# Sheet_1_2025-10-18.net
KiCad netlist of a schematic drawn in Altium Designer
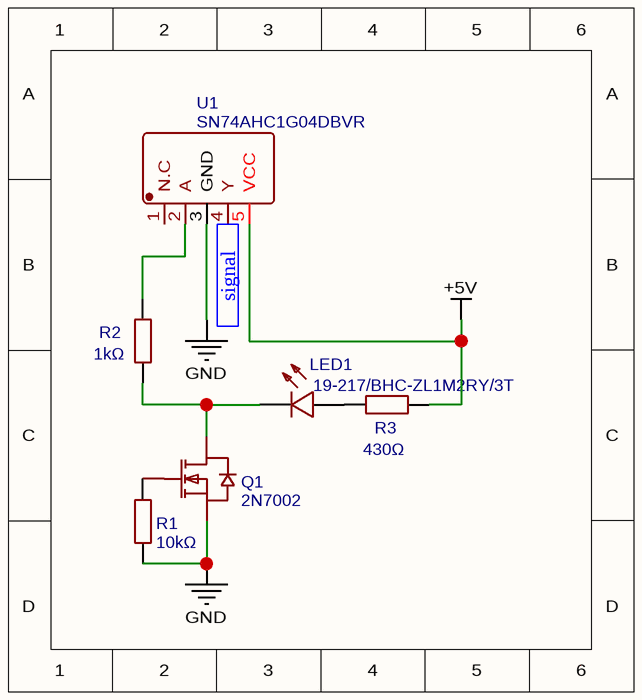
[diagram p0: Sheet_1_2025-10-18.schdoc]

(export (version "E")
  (design (tool "Eeschema 10.0.6"))
  (components
    (comp (ref "LED1")
      (value "19-217/BHC-ZL1M2RY/3T")
      (fields (field (name "MANUFACTURER") "EVERLIGHT"))
      (libsource (lib "altium-import") (part "root_0_19-217/BHC-ZL1M2RY/3T_"))
    )
    (comp (ref "Q1")
      (value "2N7002")
      (fields (field (name "MANUFACTURER") "CJ"))
      (libsource (lib "altium-import") (part "root_0_2N7002_"))
    )
    (comp (ref "R1")
      (value "10kΩ")
      (fields (field (name "MANUFACTURER") "UniOhm") (field (name "MANUFACTURER PART") "0402WGF1002TCE"))
      (libsource (lib "altium-import") (part "root_1_10kΩ_"))
    )
    (comp (ref "R2")
      (value "1kΩ")
      (fields (field (name "MANUFACTURER") "UniOhm") (field (name "MANUFACTURER PART") "0402WGF1001TCE"))
      (libsource (lib "altium-import") (part "root_3_1kΩ_"))
    )
    (comp (ref "R3")
      (value "430Ω")
      (fields (field (name "MANUFACTURER") "UniOhm") (field (name "MANUFACTURER PART") "0603WAF4300T5E"))
      (libsource (lib "altium-import") (part "root_0_430Ω_"))
    )
    (comp (ref "U1")
      (value "SN74AHC1G04DBVR")
      (fields (field (name "MANUFACTURER") "TI"))
      (libsource (lib "altium-import") (part "root_1_SN74AHC1G04DBVR_"))
    )
  )
  (nets
    (net (code "1") (name "+5V") (class "Default")
      (node (ref "R3") (pin "2") (pinfunction "2_2") (pintype "passive"))
      (node (ref "U1") (pin "5") (pinfunction "VCC_5") (pintype "passive"))
    )
    (net (code "2") (name "/signal") (class "Default")
      (node (ref "U1") (pin "4") (pinfunction "Y_4") (pintype "passive"))
    )
    (net (code "3") (name "GND") (class "Default")
      (node (ref "Q1") (pin "2") (pinfunction "S_2") (pintype "passive"))
      (node (ref "R1") (pin "1") (pinfunction "1_1") (pintype "passive"))
      (node (ref "U1") (pin "3") (pinfunction "GND_3") (pintype "passive"))
    )
    (net (code "4") (name "Net-(LED1-A)") (class "Default")
      (node (ref "LED1") (pin "1") (pinfunction "A_1") (pintype "passive"))
      (node (ref "R3") (pin "1") (pinfunction "1_1") (pintype "passive"))
    )
    (net (code "5") (name "Net-(LED1-C)") (class "Default")
      (node (ref "LED1") (pin "2") (pinfunction "C_2") (pintype "passive"))
      (node (ref "Q1") (pin "3") (pinfunction "D_3") (pintype "passive"))
      (node (ref "R2") (pin "2") (pinfunction "2_2") (pintype "passive"))
    )
    (net (code "6") (name "Net-(Q1-G)") (class "Default")
      (node (ref "Q1") (pin "1") (pinfunction "G_1") (pintype "passive"))
      (node (ref "R1") (pin "2") (pinfunction "2_2") (pintype "passive"))
    )
    (net (code "7") (name "Net-(U1-A)") (class "Default")
      (node (ref "R2") (pin "1") (pinfunction "1_1") (pintype "passive"))
      (node (ref "U1") (pin "2") (pinfunction "A_2") (pintype "passive"))
    )
    (net (code "8") (name "unconnected-(U1-N.C-Pad1)") (class "Default")
      (node (ref "U1") (pin "1") (pinfunction "N.C_1") (pintype "passive"))
    )
  )
)
